# LogicBoard-Pico.net
KiCad netlist of a schematic drawn in EAGLE
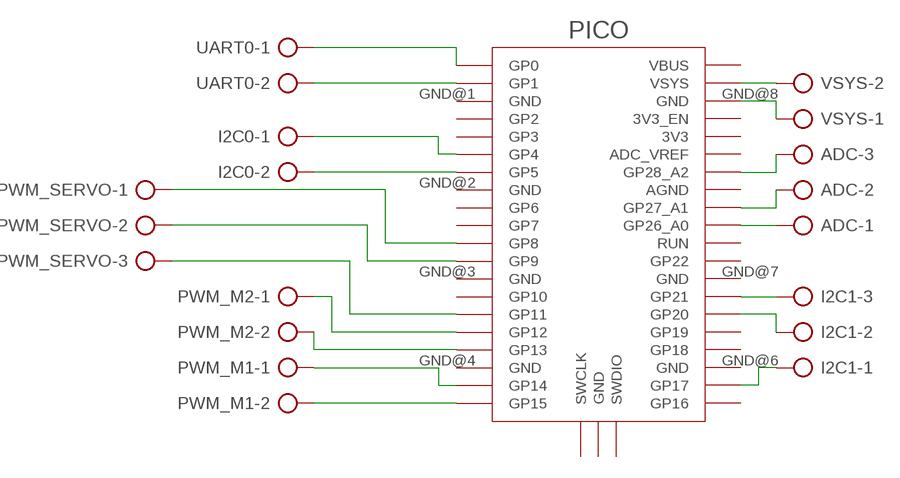
[diagram p0: schematic, sheet 1]

(export (version "E")
  (design (tool "Eeschema 10.0.6"))
  (components
    (comp (ref "ADC")
      (value "AK500/3")
      (footprint "eagle-import:AK500_3")
      (libsource (lib "eagle-import") (part "AK500/3"))
    )
    (comp (ref "I2C0")
      (value "AK500/2")
      (footprint "eagle-import:AK500_2")
      (libsource (lib "eagle-import") (part "AK500/2"))
    )
    (comp (ref "I2C1")
      (value "AK500/3")
      (footprint "eagle-import:AK500_3")
      (libsource (lib "eagle-import") (part "AK500/3"))
    )
    (comp (ref "PICO")
      (value "RPI_PICO_IG-TH")
      (footprint "eagle-import:RPI_PICO_TH")
      (libsource (lib "eagle-import") (part "RPI_PICO_IG-TH"))
    )
    (comp (ref "PWM_M1")
      (value "AK500/2")
      (footprint "eagle-import:AK500_2")
      (libsource (lib "eagle-import") (part "AK500/2"))
    )
    (comp (ref "PWM_M2")
      (value "AK500/2")
      (footprint "eagle-import:AK500_2")
      (libsource (lib "eagle-import") (part "AK500/2"))
    )
    (comp (ref "PWM_SERVO")
      (value "AK500/3")
      (footprint "eagle-import:AK500_3")
      (libsource (lib "eagle-import") (part "AK500/3"))
    )
    (comp (ref "UART0")
      (value "AK500/2")
      (footprint "eagle-import:AK500_2")
      (libsource (lib "eagle-import") (part "AK500/2"))
    )
    (comp (ref "VSYS")
      (value "AK500/2")
      (footprint "eagle-import:AK500_2")
      (libsource (lib "eagle-import") (part "AK500/2"))
    )
  )
  (nets
    (net (code "1") (name "Net-(ADCA-KL)") (class "Default")
      (node (ref "ADC") (pin "1") (pinfunction "KL_1") (pintype "passive"))
      (node (ref "PICO") (pin "GP26_A0") (pinfunction "GP26_A0_GP26_A0") (pintype "bidirectional"))
    )
    (net (code "2") (name "Net-(ADCB-KL)") (class "Default")
      (node (ref "ADC") (pin "2") (pinfunction "KL_2") (pintype "passive"))
      (node (ref "PICO") (pin "GP27_A1") (pinfunction "GP27_A1_GP27_A1") (pintype "bidirectional"))
    )
    (net (code "3") (name "Net-(ADCC-KL)") (class "Default")
      (node (ref "ADC") (pin "3") (pinfunction "KL_3") (pintype "passive"))
      (node (ref "PICO") (pin "GP28_A2") (pinfunction "GP28_A2_GP28_A2") (pintype "bidirectional"))
    )
    (net (code "4") (name "Net-(I2C0A-KL)") (class "Default")
      (node (ref "I2C0") (pin "1") (pinfunction "KL_1") (pintype "passive"))
      (node (ref "PICO") (pin "GP4") (pinfunction "GP4_GP4") (pintype "bidirectional"))
    )
    (net (code "5") (name "Net-(I2C0B-KL)") (class "Default")
      (node (ref "I2C0") (pin "2") (pinfunction "KL_2") (pintype "passive"))
      (node (ref "PICO") (pin "GP5") (pinfunction "GP5_GP5") (pintype "bidirectional"))
    )
    (net (code "6") (name "Net-(I2C1A-KL)") (class "Default")
      (node (ref "I2C1") (pin "1") (pinfunction "KL_1") (pintype "passive"))
      (node (ref "PICO") (pin "GP17") (pinfunction "GP17_GP17") (pintype "bidirectional"))
    )
    (net (code "7") (name "Net-(I2C1B-KL)") (class "Default")
      (node (ref "I2C1") (pin "2") (pinfunction "KL_2") (pintype "passive"))
      (node (ref "PICO") (pin "GP20") (pinfunction "GP20_GP20") (pintype "bidirectional"))
    )
    (net (code "8") (name "Net-(I2C1C-KL)") (class "Default")
      (node (ref "I2C1") (pin "3") (pinfunction "KL_3") (pintype "passive"))
      (node (ref "PICO") (pin "GP21") (pinfunction "GP21_GP21") (pintype "bidirectional"))
    )
    (net (code "9") (name "Net-(PWM_M1A-KL)") (class "Default")
      (node (ref "PICO") (pin "GP14") (pinfunction "GP14_GP14") (pintype "bidirectional"))
      (node (ref "PWM_M1") (pin "1") (pinfunction "KL_1") (pintype "passive"))
    )
    (net (code "10") (name "Net-(PWM_M1B-KL)") (class "Default")
      (node (ref "PICO") (pin "GP15") (pinfunction "GP15_GP15") (pintype "bidirectional"))
      (node (ref "PWM_M1") (pin "2") (pinfunction "KL_2") (pintype "passive"))
    )
    (net (code "11") (name "Net-(PWM_M2A-KL)") (class "Default")
      (node (ref "PICO") (pin "GP12") (pinfunction "GP12_GP12") (pintype "bidirectional"))
      (node (ref "PWM_M2") (pin "1") (pinfunction "KL_1") (pintype "passive"))
    )
    (net (code "12") (name "Net-(PWM_M2B-KL)") (class "Default")
      (node (ref "PICO") (pin "GP13") (pinfunction "GP13_GP13") (pintype "bidirectional"))
      (node (ref "PWM_M2") (pin "2") (pinfunction "KL_2") (pintype "passive"))
    )
    (net (code "13") (name "Net-(PWM_SERVOA-KL)") (class "Default")
      (node (ref "PICO") (pin "GP8") (pinfunction "GP8_GP8") (pintype "bidirectional"))
      (node (ref "PWM_SERVO") (pin "1") (pinfunction "KL_1") (pintype "passive"))
    )
    (net (code "14") (name "Net-(PWM_SERVOB-KL)") (class "Default")
      (node (ref "PICO") (pin "GP9") (pinfunction "GP9_GP9") (pintype "bidirectional"))
      (node (ref "PWM_SERVO") (pin "2") (pinfunction "KL_2") (pintype "passive"))
    )
    (net (code "15") (name "Net-(PWM_SERVOC-KL)") (class "Default")
      (node (ref "PICO") (pin "GP11") (pinfunction "GP11_GP11") (pintype "bidirectional"))
      (node (ref "PWM_SERVO") (pin "3") (pinfunction "KL_3") (pintype "passive"))
    )
    (net (code "16") (name "Net-(UART0A-KL)") (class "Default")
      (node (ref "PICO") (pin "GP0") (pinfunction "GP0_GP0") (pintype "bidirectional"))
      (node (ref "UART0") (pin "1") (pinfunction "KL_1") (pintype "passive"))
    )
    (net (code "17") (name "Net-(UART0B-KL)") (class "Default")
      (node (ref "PICO") (pin "GP1") (pinfunction "GP1_GP1") (pintype "bidirectional"))
      (node (ref "UART0") (pin "2") (pinfunction "KL_2") (pintype "passive"))
    )
    (net (code "18") (name "Net-(VSYSA-KL)") (class "Default")
      (node (ref "PICO") (pin "GND@8") (pinfunction "GND_GND@8") (pintype "bidirectional"))
      (node (ref "VSYS") (pin "1") (pinfunction "KL_1") (pintype "passive"))
    )
    (net (code "19") (name "Net-(VSYSB-KL)") (class "Default")
      (node (ref "PICO") (pin "VSYS") (pinfunction "VSYS_VSYS") (pintype "bidirectional"))
      (node (ref "VSYS") (pin "2") (pinfunction "KL_2") (pintype "passive"))
    )
    (net (code "20") (name "unconnected-(PICO-GND-PadGND@1)") (class "Default")
      (node (ref "PICO") (pin "GND@1") (pinfunction "GND_GND@1") (pintype "bidirectional"))
    )
    (net (code "21") (name "unconnected-(PICO-GND-PadGND@2)") (class "Default")
      (node (ref "PICO") (pin "GND@2") (pinfunction "GND_GND@2") (pintype "bidirectional"))
    )
    (net (code "22") (name "unconnected-(PICO-GND-PadGND@3)") (class "Default")
      (node (ref "PICO") (pin "GND@3") (pinfunction "GND_GND@3") (pintype "bidirectional"))
    )
    (net (code "23") (name "unconnected-(PICO-GND-PadGND@4)") (class "Default")
      (node (ref "PICO") (pin "GND@4") (pinfunction "GND_GND@4") (pintype "bidirectional"))
    )
    (net (code "24") (name "unconnected-(PICO-GND-PadGND@5)") (class "Default")
      (node (ref "PICO") (pin "GND@5") (pinfunction "GND_GND@5") (pintype "bidirectional"))
    )
    (net (code "25") (name "unconnected-(PICO-GND-PadGND@6)") (class "Default")
      (node (ref "PICO") (pin "GND@6") (pinfunction "GND_GND@6") (pintype "bidirectional"))
    )
    (net (code "26") (name "unconnected-(PICO-GND-PadGND@7)") (class "Default")
      (node (ref "PICO") (pin "GND@7") (pinfunction "GND_GND@7") (pintype "bidirectional"))
    )
    (net (code "27") (name "unconnected-(PICO-Pad3V3)") (class "Default")
      (node (ref "PICO") (pin "3V3") (pinfunction "3V3_3V3") (pintype "bidirectional"))
    )
    (net (code "28") (name "unconnected-(PICO-Pad3V3_EN)") (class "Default")
      (node (ref "PICO") (pin "3V3_EN") (pinfunction "3V3_EN_3V3_EN") (pintype "bidirectional"))
    )
    (net (code "29") (name "unconnected-(PICO-PadADC_VREF)") (class "Default")
      (node (ref "PICO") (pin "ADC_VREF") (pinfunction "ADC_VREF_ADC_VREF") (pintype "bidirectional"))
    )
    (net (code "30") (name "unconnected-(PICO-PadAGND)") (class "Default")
      (node (ref "PICO") (pin "AGND") (pinfunction "AGND_AGND") (pintype "bidirectional"))
    )
    (net (code "31") (name "unconnected-(PICO-PadGP2)") (class "Default")
      (node (ref "PICO") (pin "GP2") (pinfunction "GP2_GP2") (pintype "bidirectional"))
    )
    (net (code "32") (name "unconnected-(PICO-PadGP3)") (class "Default")
      (node (ref "PICO") (pin "GP3") (pinfunction "GP3_GP3") (pintype "bidirectional"))
    )
    (net (code "33") (name "unconnected-(PICO-PadGP6)") (class "Default")
      (node (ref "PICO") (pin "GP6") (pinfunction "GP6_GP6") (pintype "bidirectional"))
    )
    (net (code "34") (name "unconnected-(PICO-PadGP7)") (class "Default")
      (node (ref "PICO") (pin "GP7") (pinfunction "GP7_GP7") (pintype "bidirectional"))
    )
    (net (code "35") (name "unconnected-(PICO-PadGP10)") (class "Default")
      (node (ref "PICO") (pin "GP10") (pinfunction "GP10_GP10") (pintype "bidirectional"))
    )
    (net (code "36") (name "unconnected-(PICO-PadGP16)") (class "Default")
      (node (ref "PICO") (pin "GP16") (pinfunction "GP16_GP16") (pintype "bidirectional"))
    )
    (net (code "37") (name "unconnected-(PICO-PadGP18)") (class "Default")
      (node (ref "PICO") (pin "GP18") (pinfunction "GP18_GP18") (pintype "bidirectional"))
    )
    (net (code "38") (name "unconnected-(PICO-PadGP19)") (class "Default")
      (node (ref "PICO") (pin "GP19") (pinfunction "GP19_GP19") (pintype "bidirectional"))
    )
    (net (code "39") (name "unconnected-(PICO-PadGP22)") (class "Default")
      (node (ref "PICO") (pin "GP22") (pinfunction "GP22_GP22") (pintype "bidirectional"))
    )
    (net (code "40") (name "unconnected-(PICO-PadRUN)") (class "Default")
      (node (ref "PICO") (pin "RUN") (pinfunction "RUN_RUN") (pintype "bidirectional"))
    )
    (net (code "41") (name "unconnected-(PICO-PadSWCLK)") (class "Default")
      (node (ref "PICO") (pin "SWCLK") (pinfunction "SWCLK_SWCLK") (pintype "bidirectional"))
    )
    (net (code "42") (name "unconnected-(PICO-PadSWDIO)") (class "Default")
      (node (ref "PICO") (pin "SWDIO") (pinfunction "SWDIO_SWDIO") (pintype "bidirectional"))
    )
    (net (code "43") (name "unconnected-(PICO-PadVBUS)") (class "Default")
      (node (ref "PICO") (pin "VBUS") (pinfunction "VBUS_VBUS") (pintype "bidirectional"))
    )
  )
)
